# controller_Ilham_Widyo_Nugroho_SM.net
KiCad netlist of a schematic drawn in EAGLE
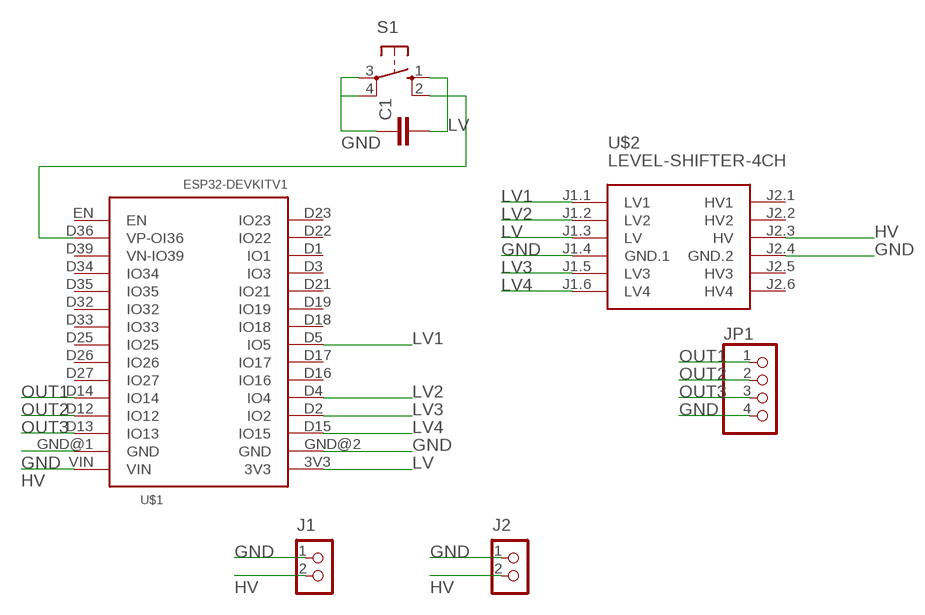
[diagram p0: schematic, sheet 1]

(export (version "E")
  (design (tool "Eeschema 10.0.6"))
  (components
    (comp (ref "C1")
      (value "C-EU025-025X050")
      (footprint "eagle-import:C025-025X050")
      (libsource (lib "eagle-import") (part "C-EU025-025X050"))
    )
    (comp (ref "J1")
      (value "CON_TERMINAL_BLOCK_02-5MM")
      (footprint "eagle-import:TERMINAL_BLOCK_2P_5")
      (libsource (lib "eagle-import") (part "CON_TERMINAL_BLOCK_02-5MM"))
    )
    (comp (ref "J2")
      (value "CON_TERMINAL_BLOCK_02-5MM")
      (footprint "eagle-import:TERMINAL_BLOCK_2P_5")
      (libsource (lib "eagle-import") (part "CON_TERMINAL_BLOCK_02-5MM"))
    )
    (comp (ref "JP1")
      (value "PINHD-1X4")
      (footprint "eagle-import:1X04")
      (libsource (lib "eagle-import") (part "PINHD-1X4"))
    )
    (comp (ref "S1")
      (value "10-XX")
      (footprint "eagle-import:B3F-10XX")
      (fields (field (name "MPN") "B3F-1000"))
      (libsource (lib "eagle-import") (part "10-XX"))
    )
    (comp (ref "U$1")
      (value "ESP32DEVKITV1")
      (footprint "eagle-import:ESP32-DEVKITV1")
      (libsource (lib "eagle-import") (part "ESP32DEVKITV1"))
    )
    (comp (ref "U$2")
      (value "LEVEL-SHIFTER-4CH")
      (footprint "eagle-import:LEVEL-SHIFTER-4CH")
      (libsource (lib "eagle-import") (part "LEVEL-SHIFTER-4CH"))
    )
  )
  (nets
    (net (code "1") (name "/GND") (class "Default")
      (node (ref "C1") (pin "1") (pinfunction "1_1") (pintype "passive"))
      (node (ref "J1") (pin "1") (pinfunction "1_1") (pintype "passive"))
      (node (ref "J2") (pin "1") (pinfunction "1_1") (pintype "passive"))
      (node (ref "JP1") (pin "4") (pinfunction "4_4") (pintype "passive"))
      (node (ref "S1") (pin "3") (pinfunction "P_3") (pintype "passive"))
      (node (ref "S1") (pin "4") (pinfunction "P1_4") (pintype "passive"))
      (node (ref "U$1") (pin "GND@1") (pinfunction "GND_GND@1") (pintype "bidirectional"))
      (node (ref "U$1") (pin "GND@2") (pinfunction "GND_GND@2") (pintype "bidirectional"))
      (node (ref "U$2") (pin "J1.4") (pinfunction "GND.1_J1.4") (pintype "power_in"))
      (node (ref "U$2") (pin "J2.4") (pinfunction "GND.2_J2.4") (pintype "power_in"))
    )
    (net (code "2") (name "/HV") (class "Default")
      (node (ref "J1") (pin "2") (pinfunction "2_2") (pintype "passive"))
      (node (ref "J2") (pin "2") (pinfunction "2_2") (pintype "passive"))
      (node (ref "U$1") (pin "VIN") (pinfunction "VIN_VIN") (pintype "bidirectional"))
      (node (ref "U$2") (pin "J2.3") (pinfunction "HV_J2.3") (pintype "power_in"))
    )
    (net (code "3") (name "/LV") (class "Default")
      (node (ref "C1") (pin "2") (pinfunction "2_2") (pintype "passive"))
      (node (ref "S1") (pin "1") (pinfunction "S_1") (pintype "passive"))
      (node (ref "S1") (pin "2") (pinfunction "S1_2") (pintype "passive"))
      (node (ref "U$1") (pin "3V3") (pinfunction "3V3_3V3") (pintype "bidirectional"))
      (node (ref "U$1") (pin "D36") (pinfunction "VP-OI36_D36") (pintype "bidirectional"))
      (node (ref "U$2") (pin "J1.3") (pinfunction "LV_J1.3") (pintype "power_in"))
    )
    (net (code "4") (name "/LV1") (class "Default")
      (node (ref "U$1") (pin "D5") (pinfunction "IO5_D5") (pintype "bidirectional"))
      (node (ref "U$2") (pin "J1.1") (pinfunction "LV1_J1.1") (pintype "bidirectional"))
    )
    (net (code "5") (name "/LV2") (class "Default")
      (node (ref "U$1") (pin "D4") (pinfunction "IO4_D4") (pintype "bidirectional"))
      (node (ref "U$2") (pin "J1.2") (pinfunction "LV2_J1.2") (pintype "bidirectional"))
    )
    (net (code "6") (name "/LV3") (class "Default")
      (node (ref "U$1") (pin "D2") (pinfunction "IO2_D2") (pintype "bidirectional"))
      (node (ref "U$2") (pin "J1.5") (pinfunction "LV3_J1.5") (pintype "bidirectional"))
    )
    (net (code "7") (name "/LV4") (class "Default")
      (node (ref "U$1") (pin "D15") (pinfunction "IO15_D15") (pintype "bidirectional"))
      (node (ref "U$2") (pin "J1.6") (pinfunction "LV4_J1.6") (pintype "bidirectional"))
    )
    (net (code "8") (name "/OUT1") (class "Default")
      (node (ref "JP1") (pin "1") (pinfunction "1_1") (pintype "passive"))
      (node (ref "U$1") (pin "D14") (pinfunction "IO14_D14") (pintype "bidirectional"))
    )
    (net (code "9") (name "/OUT2") (class "Default")
      (node (ref "JP1") (pin "2") (pinfunction "2_2") (pintype "passive"))
      (node (ref "U$1") (pin "D12") (pinfunction "IO12_D12") (pintype "bidirectional"))
    )
    (net (code "10") (name "/OUT3") (class "Default")
      (node (ref "JP1") (pin "3") (pinfunction "3_3") (pintype "passive"))
      (node (ref "U$1") (pin "D13") (pinfunction "IO13_D13") (pintype "bidirectional"))
    )
    (net (code "11") (name "unconnected-(U$1-IO1-PadD1)") (class "Default")
      (node (ref "U$1") (pin "D1") (pinfunction "IO1_D1") (pintype "bidirectional"))
    )
    (net (code "12") (name "unconnected-(U$1-IO3-PadD3)") (class "Default")
      (node (ref "U$1") (pin "D3") (pinfunction "IO3_D3") (pintype "bidirectional"))
    )
    (net (code "13") (name "unconnected-(U$1-IO16-PadD16)") (class "Default")
      (node (ref "U$1") (pin "D16") (pinfunction "IO16_D16") (pintype "bidirectional"))
    )
    (net (code "14") (name "unconnected-(U$1-IO17-PadD17)") (class "Default")
      (node (ref "U$1") (pin "D17") (pinfunction "IO17_D17") (pintype "bidirectional"))
    )
    (net (code "15") (name "unconnected-(U$1-IO18-PadD18)") (class "Default")
      (node (ref "U$1") (pin "D18") (pinfunction "IO18_D18") (pintype "bidirectional"))
    )
    (net (code "16") (name "unconnected-(U$1-IO19-PadD19)") (class "Default")
      (node (ref "U$1") (pin "D19") (pinfunction "IO19_D19") (pintype "bidirectional"))
    )
    (net (code "17") (name "unconnected-(U$1-IO21-PadD21)") (class "Default")
      (node (ref "U$1") (pin "D21") (pinfunction "IO21_D21") (pintype "bidirectional"))
    )
    (net (code "18") (name "unconnected-(U$1-IO22-PadD22)") (class "Default")
      (node (ref "U$1") (pin "D22") (pinfunction "IO22_D22") (pintype "bidirectional"))
    )
    (net (code "19") (name "unconnected-(U$1-IO23-PadD23)") (class "Default")
      (node (ref "U$1") (pin "D23") (pinfunction "IO23_D23") (pintype "bidirectional"))
    )
    (net (code "20") (name "unconnected-(U$1-IO25-PadD25)") (class "Default")
      (node (ref "U$1") (pin "D25") (pinfunction "IO25_D25") (pintype "bidirectional"))
    )
    (net (code "21") (name "unconnected-(U$1-IO26-PadD26)") (class "Default")
      (node (ref "U$1") (pin "D26") (pinfunction "IO26_D26") (pintype "bidirectional"))
    )
    (net (code "22") (name "unconnected-(U$1-IO27-PadD27)") (class "Default")
      (node (ref "U$1") (pin "D27") (pinfunction "IO27_D27") (pintype "bidirectional"))
    )
    (net (code "23") (name "unconnected-(U$1-IO32-PadD32)") (class "Default")
      (node (ref "U$1") (pin "D32") (pinfunction "IO32_D32") (pintype "bidirectional"))
    )
    (net (code "24") (name "unconnected-(U$1-IO33-PadD33)") (class "Default")
      (node (ref "U$1") (pin "D33") (pinfunction "IO33_D33") (pintype "bidirectional"))
    )
    (net (code "25") (name "unconnected-(U$1-IO34-PadD34)") (class "Default")
      (node (ref "U$1") (pin "D34") (pinfunction "IO34_D34") (pintype "bidirectional"))
    )
    (net (code "26") (name "unconnected-(U$1-IO35-PadD35)") (class "Default")
      (node (ref "U$1") (pin "D35") (pinfunction "IO35_D35") (pintype "bidirectional"))
    )
    (net (code "27") (name "unconnected-(U$1-PadEN)") (class "Default")
      (node (ref "U$1") (pin "EN") (pinfunction "EN_EN") (pintype "bidirectional"))
    )
    (net (code "28") (name "unconnected-(U$1-VN-IO39-PadD39)") (class "Default")
      (node (ref "U$1") (pin "D39") (pinfunction "VN-IO39_D39") (pintype "bidirectional"))
    )
    (net (code "29") (name "unconnected-(U$2-HV1-PadJ2.1)") (class "Default")
      (node (ref "U$2") (pin "J2.1") (pinfunction "HV1_J2.1") (pintype "bidirectional"))
    )
    (net (code "30") (name "unconnected-(U$2-HV2-PadJ2.2)") (class "Default")
      (node (ref "U$2") (pin "J2.2") (pinfunction "HV2_J2.2") (pintype "bidirectional"))
    )
    (net (code "31") (name "unconnected-(U$2-HV3-PadJ2.5)") (class "Default")
      (node (ref "U$2") (pin "J2.5") (pinfunction "HV3_J2.5") (pintype "bidirectional"))
    )
    (net (code "32") (name "unconnected-(U$2-HV4-PadJ2.6)") (class "Default")
      (node (ref "U$2") (pin "J2.6") (pinfunction "HV4_J2.6") (pintype "bidirectional"))
    )
  )
)
